# 2015_AdaptateurBluetooth.net
KiCad netlist of a schematic drawn in Altium Designer
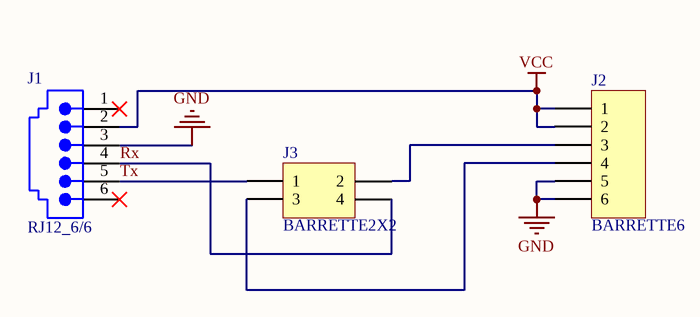
[diagram p0: 2015_AdaptateurBluetooth.SchDoc]

(export (version "E")
  (design (tool "Eeschema 10.0.6"))
  (components
    (comp (ref "J1")
      (value "RJ12_6/6")
      (footprint "RJ12_6/6")
      (description "EMBASE RJ12_6/6 COUDEE")
      (fields (field (name "TYPE") "RJ12_6/6"))
      (libsource (lib "connecteurs") (part "RJ12_6/6"))
    )
    (comp (ref "J2")
      (value "BARRETTE6")
      (footprint "BARRETTE_6_F_D")
      (description "Header, 6-Pin")
      (fields (field (name "PUBLISHER") "Altium Limited"))
      (libsource (lib "Connecteur") (part "BARRETTE6"))
    )
    (comp (ref "J3")
      (value "BARRETTE2X2")
      (footprint "BARRETTE_2X2_F_D")
      (description "Header, 2-Pin, Dual row")
      (fields (field (name "PUBLISHER") "Altium Limited"))
      (libsource (lib "Connecteur") (part "BARRETTE2X2"))
    )
  )
  (nets
    (net (code "1") (name "/Rx") (class "Default")
      (node (ref "J1") (pin "4") (pinfunction "4_4") (pintype "passive"))
      (node (ref "J3") (pin "4") (pinfunction "4_4") (pintype "passive"))
    )
    (net (code "2") (name "/Tx") (class "Default")
      (node (ref "J1") (pin "5") (pinfunction "5_5") (pintype "passive"))
      (node (ref "J3") (pin "1") (pinfunction "1_1") (pintype "passive"))
    )
    (net (code "3") (name "GND") (class "Default")
      (node (ref "J1") (pin "3") (pinfunction "3_3") (pintype "passive"))
      (node (ref "J2") (pin "5") (pinfunction "5_5") (pintype "passive"))
      (node (ref "J2") (pin "6") (pinfunction "6_6") (pintype "passive"))
    )
    (net (code "4") (name "Net-(J2-Pad3)") (class "Default")
      (node (ref "J2") (pin "3") (pinfunction "3_3") (pintype "passive"))
      (node (ref "J3") (pin "2") (pinfunction "2_2") (pintype "passive"))
    )
    (net (code "5") (name "Net-(J2-Pad4)") (class "Default")
      (node (ref "J2") (pin "4") (pinfunction "4_4") (pintype "passive"))
      (node (ref "J3") (pin "3") (pinfunction "3_3") (pintype "passive"))
    )
    (net (code "6") (name "VCC") (class "Default")
      (node (ref "J1") (pin "2") (pinfunction "2_2") (pintype "passive"))
      (node (ref "J2") (pin "1") (pinfunction "1_1") (pintype "passive"))
      (node (ref "J2") (pin "2") (pinfunction "2_2") (pintype "passive"))
    )
    (net (code "7") (name "unconnected-(J1-Pad1)") (class "Default")
      (node (ref "J1") (pin "1") (pinfunction "1_1") (pintype "passive+no_connect"))
    )
    (net (code "8") (name "unconnected-(J1-Pad6)") (class "Default")
      (node (ref "J1") (pin "6") (pinfunction "6_6") (pintype "passive+no_connect"))
    )
  )
)
